# ESP07_Multi.net
KiCad netlist of a schematic drawn in EAGLE
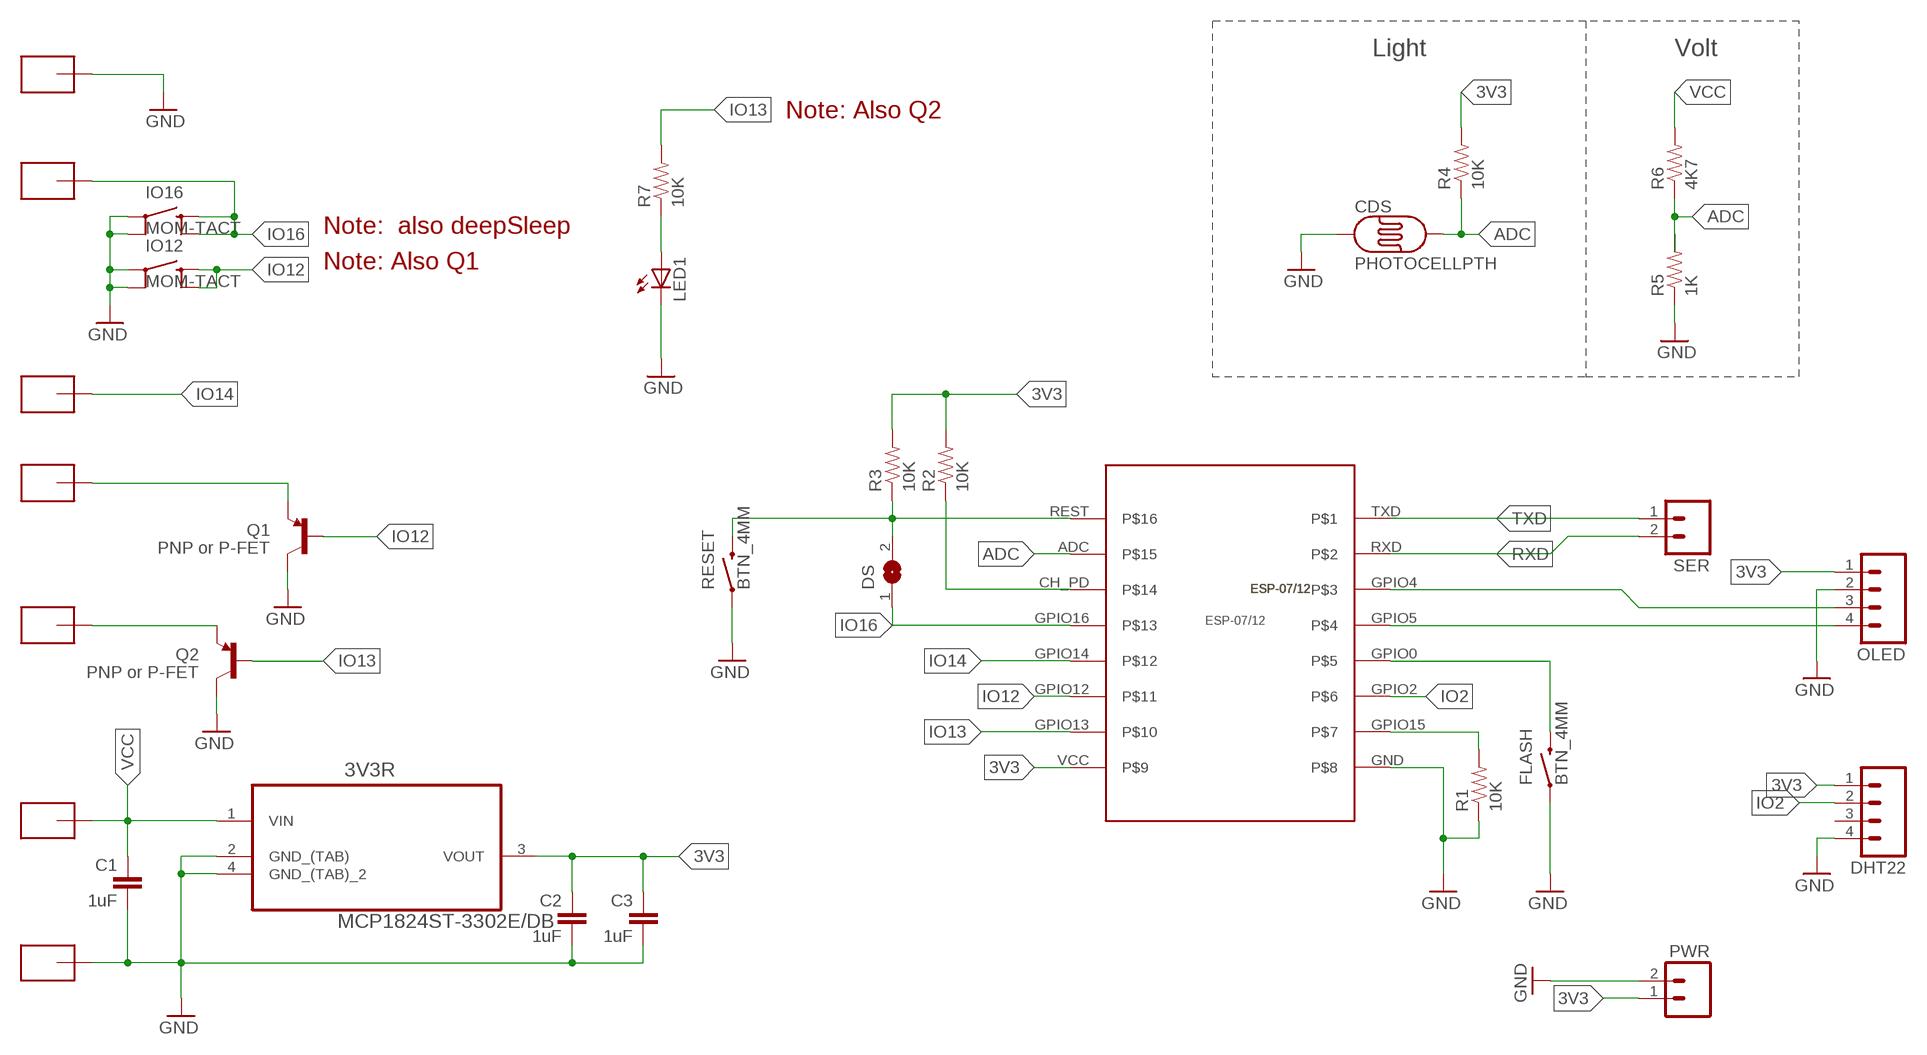
[diagram p0: schematic, sheet 1]

(export (version "E")
  (design (tool "Eeschema 10.0.6"))
  (components
    (comp (ref "3V3R")
      (value "MCP1824ST-3302E/DB")
      (footprint "eagle-import:SOT230P700X180-4N")
      (libsource (lib "eagle-import") (part "MCP1824ST-3302E/DB"))
    )
    (comp (ref "C1")
      (value "1uF")
      (footprint "eagle-import:0805-CAP")
      (libsource (lib "eagle-import") (part "CAP"))
    )
    (comp (ref "C2")
      (value "1uF")
      (footprint "eagle-import:0805-CAP")
      (libsource (lib "eagle-import") (part "CAP"))
    )
    (comp (ref "C3")
      (value "1uF")
      (footprint "eagle-import:0805-CAP")
      (libsource (lib "eagle-import") (part "CAP"))
    )
    (comp (ref "CDS")
      (value "PHOTOCELLPTH")
      (footprint "eagle-import:PHOTOCELL")
      (libsource (lib "eagle-import") (part "PHOTOCELLPTH"))
    )
    (comp (ref "DHT22")
      (value "M04PTH")
      (footprint "eagle-import:1X04")
      (libsource (lib "eagle-import") (part "M04PTH"))
    )
    (comp (ref "DS") (value "SJ") (footprint "eagle-import:SJ") (libsource (lib "eagle-import") (part "SJ")))
    (comp (ref "FLASH")
      (value "BTN_4MM")
      (footprint "eagle-import:BTN_4MM")
      (libsource (lib "eagle-import") (part "BTN_4MM"))
    )
    (comp (ref "IO12")
      (value "MOM-TACT")
      (footprint "eagle-import:TACTILE-SMD")
      (libsource (lib "eagle-import") (part "MOM-TACT"))
    )
    (comp (ref "IO16")
      (value "MOM-TACT")
      (footprint "eagle-import:TACTILE-SMD")
      (libsource (lib "eagle-import") (part "MOM-TACT"))
    )
    (comp (ref "LED1")
      (value "LEDCHIPLED_0805")
      (footprint "eagle-import:CHIPLED_0805")
      (libsource (lib "eagle-import") (part "LEDCHIPLED_0805"))
    )
    (comp (ref "OLED")
      (value "M04PTH")
      (footprint "eagle-import:1X04")
      (libsource (lib "eagle-import") (part "M04PTH"))
    )
    (comp (ref "PWR")
      (value "M02PTH")
      (footprint "eagle-import:1X02")
      (libsource (lib "eagle-import") (part "M02PTH"))
    )
    (comp (ref "Q1")
      (value "PNP or P-FET")
      (footprint "eagle-import:SOT23-3")
      (libsource (lib "eagle-import") (part "TRANSISTOR_PNPSMD"))
    )
    (comp (ref "Q2")
      (value "PNP or P-FET")
      (footprint "eagle-import:SOT23-3")
      (libsource (lib "eagle-import") (part "TRANSISTOR_PNPSMD"))
    )
    (comp (ref "R1")
      (value "10K")
      (footprint "eagle-import:0805")
      (libsource (lib "eagle-import") (part "RESISTOR0805-RES"))
    )
    (comp (ref "R2")
      (value "10K")
      (footprint "eagle-import:0805")
      (libsource (lib "eagle-import") (part "RESISTOR0805-RES"))
    )
    (comp (ref "R3")
      (value "10K")
      (footprint "eagle-import:0805")
      (libsource (lib "eagle-import") (part "RESISTOR0805-RES"))
    )
    (comp (ref "R4")
      (value "10K")
      (footprint "eagle-import:0805")
      (libsource (lib "eagle-import") (part "RESISTOR0805-RES"))
    )
    (comp (ref "R5")
      (value "1K")
      (footprint "eagle-import:0805")
      (libsource (lib "eagle-import") (part "RESISTOR0805-RES"))
    )
    (comp (ref "R6")
      (value "4K7")
      (footprint "eagle-import:0805")
      (libsource (lib "eagle-import") (part "RESISTOR0805-RES"))
    )
    (comp (ref "R7")
      (value "10K")
      (footprint "eagle-import:0805")
      (libsource (lib "eagle-import") (part "RESISTOR0805-RES"))
    )
    (comp (ref "RESET")
      (value "BTN_4MM")
      (footprint "eagle-import:BTN_4MM")
      (libsource (lib "eagle-import") (part "BTN_4MM"))
    )
    (comp (ref "SER")
      (value "M02PTH")
      (footprint "eagle-import:1X02")
      (libsource (lib "eagle-import") (part "M02PTH"))
    )
    (comp (ref "U$1")
      (value "ESP-07/12")
      (footprint "eagle-import:ESP-07_12")
      (libsource (lib "eagle-import") (part "ESP-07/12"))
    )
    (comp (ref "U$2")
      (value "SMD-PAD-SM")
      (footprint "eagle-import:SMD-PAD3")
      (libsource (lib "eagle-import") (part "SMD-PAD-SM"))
    )
    (comp (ref "U$3")
      (value "SMD-PAD-SM")
      (footprint "eagle-import:SMD-PAD3")
      (libsource (lib "eagle-import") (part "SMD-PAD-SM"))
    )
    (comp (ref "U$4")
      (value "SMD-PAD-SM")
      (footprint "eagle-import:SMD-PAD3")
      (libsource (lib "eagle-import") (part "SMD-PAD-SM"))
    )
    (comp (ref "U$5")
      (value "SMD-PAD-SM")
      (footprint "eagle-import:SMD-PAD3")
      (libsource (lib "eagle-import") (part "SMD-PAD-SM"))
    )
    (comp (ref "U$6")
      (value "SMD-PAD-SM")
      (footprint "eagle-import:SMD-PAD3")
      (libsource (lib "eagle-import") (part "SMD-PAD-SM"))
    )
    (comp (ref "U$7")
      (value "SMD-PAD-SM")
      (footprint "eagle-import:SMD-PAD3")
      (libsource (lib "eagle-import") (part "SMD-PAD-SM"))
    )
    (comp (ref "U$8")
      (value "SMD-PAD-SM")
      (footprint "eagle-import:SMD-PAD3")
      (libsource (lib "eagle-import") (part "SMD-PAD-SM"))
    )
  )
  (nets
    (net (code "1") (name "3V3") (class "Default")
      (node (ref "3V3R") (pin "3") (pinfunction "VOUT_3") (pintype "output"))
      (node (ref "C2") (pin "1") (pinfunction "1_1") (pintype "passive"))
      (node (ref "C3") (pin "1") (pinfunction "1_1") (pintype "passive"))
      (node (ref "DHT22") (pin "1") (pinfunction "1_1") (pintype "passive"))
      (node (ref "OLED") (pin "1") (pinfunction "1_1") (pintype "passive"))
      (node (ref "PWR") (pin "1") (pinfunction "1_1") (pintype "passive"))
      (node (ref "R2") (pin "2") (pinfunction "2_2") (pintype "passive"))
      (node (ref "R3") (pin "2") (pinfunction "2_2") (pintype "passive"))
      (node (ref "R4") (pin "2") (pinfunction "2_2") (pintype "passive"))
      (node (ref "U$1") (pin "VCC") (pinfunction "P$9_VCC") (pintype "bidirectional"))
    )
    (net (code "2") (name "ADC") (class "Default")
      (node (ref "CDS") (pin "2") (pinfunction "P$2_2") (pintype "bidirectional"))
      (node (ref "R4") (pin "1") (pinfunction "1_1") (pintype "passive"))
      (node (ref "R5") (pin "2") (pinfunction "2_2") (pintype "passive"))
      (node (ref "R6") (pin "1") (pinfunction "1_1") (pintype "passive"))
      (node (ref "U$1") (pin "ADC") (pinfunction "P$15_ADC") (pintype "bidirectional"))
    )
    (net (code "3") (name "GND") (class "Default")
      (node (ref "3V3R") (pin "2") (pinfunction "GND_(TAB)_2") (pintype "passive"))
      (node (ref "3V3R") (pin "4") (pinfunction "GND_(TAB)_2_4") (pintype "passive"))
      (node (ref "C1") (pin "2") (pinfunction "2_2") (pintype "passive"))
      (node (ref "C2") (pin "2") (pinfunction "2_2") (pintype "passive"))
      (node (ref "C3") (pin "2") (pinfunction "2_2") (pintype "passive"))
      (node (ref "CDS") (pin "1") (pinfunction "P$1_1") (pintype "bidirectional"))
      (node (ref "DHT22") (pin "4") (pinfunction "4_4") (pintype "passive"))
      (node (ref "FLASH") (pin "1") (pinfunction "1_1") (pintype "passive"))
      (node (ref "IO12") (pin "1") (pinfunction "1_1") (pintype "passive"))
      (node (ref "IO12") (pin "2") (pinfunction "3_2") (pintype "passive"))
      (node (ref "IO16") (pin "1") (pinfunction "1_1") (pintype "passive"))
      (node (ref "IO16") (pin "2") (pinfunction "3_2") (pintype "passive"))
      (node (ref "LED1") (pin "C") (pinfunction "C_C") (pintype "passive"))
      (node (ref "OLED") (pin "2") (pinfunction "2_2") (pintype "passive"))
      (node (ref "PWR") (pin "2") (pinfunction "2_2") (pintype "passive"))
      (node (ref "Q1") (pin "3") (pinfunction "C_3") (pintype "passive"))
      (node (ref "Q2") (pin "3") (pinfunction "C_3") (pintype "passive"))
      (node (ref "R1") (pin "1") (pinfunction "1_1") (pintype "passive"))
      (node (ref "R5") (pin "1") (pinfunction "1_1") (pintype "passive"))
      (node (ref "RESET") (pin "1") (pinfunction "1_1") (pintype "passive"))
      (node (ref "U$1") (pin "GND") (pinfunction "P$8_GND") (pintype "bidirectional"))
      (node (ref "U$2") (pin "P$1") (pinfunction "P$1_P$1") (pintype "bidirectional"))
      (node (ref "U$5") (pin "P$1") (pinfunction "P$1_P$1") (pintype "bidirectional"))
    )
    (net (code "4") (name "IO2") (class "Default")
      (node (ref "DHT22") (pin "2") (pinfunction "2_2") (pintype "passive"))
      (node (ref "U$1") (pin "GPIO2") (pinfunction "P$6_GPIO2") (pintype "bidirectional"))
    )
    (net (code "5") (name "IO12") (class "Default")
      (node (ref "IO12") (pin "3") (pinfunction "2_3") (pintype "passive"))
      (node (ref "IO12") (pin "4") (pinfunction "4_4") (pintype "passive"))
      (node (ref "Q1") (pin "1") (pinfunction "B_1") (pintype "passive"))
      (node (ref "U$1") (pin "GPIO12") (pinfunction "P$11_GPIO12") (pintype "bidirectional"))
    )
    (net (code "6") (name "IO13") (class "Default")
      (node (ref "Q2") (pin "1") (pinfunction "B_1") (pintype "passive"))
      (node (ref "R7") (pin "2") (pinfunction "2_2") (pintype "passive"))
      (node (ref "U$1") (pin "GPIO13") (pinfunction "P$10_GPIO13") (pintype "bidirectional"))
    )
    (net (code "7") (name "IO14") (class "Default")
      (node (ref "U$1") (pin "GPIO14") (pinfunction "P$12_GPIO14") (pintype "bidirectional"))
      (node (ref "U$4") (pin "P$1") (pinfunction "P$1_P$1") (pintype "bidirectional"))
    )
    (net (code "8") (name "IO16") (class "Default")
      (node (ref "DS") (pin "1") (pinfunction "1_1") (pintype "passive"))
      (node (ref "IO16") (pin "3") (pinfunction "2_3") (pintype "passive"))
      (node (ref "IO16") (pin "4") (pinfunction "4_4") (pintype "passive"))
      (node (ref "U$1") (pin "GPIO16") (pinfunction "P$13_GPIO16") (pintype "bidirectional"))
      (node (ref "U$6") (pin "P$1") (pinfunction "P$1_P$1") (pintype "bidirectional"))
    )
    (net (code "9") (name "Net-(LED1-PadA)") (class "Default")
      (node (ref "LED1") (pin "A") (pinfunction "A_A") (pintype "passive"))
      (node (ref "R7") (pin "1") (pinfunction "1_1") (pintype "passive"))
    )
    (net (code "10") (name "Net-(Q1-E)") (class "Default")
      (node (ref "Q1") (pin "2") (pinfunction "E_2") (pintype "passive"))
      (node (ref "U$7") (pin "P$1") (pinfunction "P$1_P$1") (pintype "bidirectional"))
    )
    (net (code "11") (name "Net-(Q2-E)") (class "Default")
      (node (ref "Q2") (pin "2") (pinfunction "E_2") (pintype "passive"))
      (node (ref "U$8") (pin "P$1") (pinfunction "P$1_P$1") (pintype "bidirectional"))
    )
    (net (code "12") (name "Net-(U$1-P$3)") (class "Default")
      (node (ref "OLED") (pin "3") (pinfunction "3_3") (pintype "passive"))
      (node (ref "U$1") (pin "GPIO4") (pinfunction "P$3_GPIO4") (pintype "bidirectional"))
    )
    (net (code "13") (name "Net-(U$1-P$4)") (class "Default")
      (node (ref "OLED") (pin "4") (pinfunction "4_4") (pintype "passive"))
      (node (ref "U$1") (pin "GPIO5") (pinfunction "P$4_GPIO5") (pintype "bidirectional"))
    )
    (net (code "14") (name "Net-(U$1-P$5)") (class "Default")
      (node (ref "FLASH") (pin "2") (pinfunction "2_2") (pintype "passive"))
      (node (ref "U$1") (pin "GPIO0") (pinfunction "P$5_GPIO0") (pintype "bidirectional"))
    )
    (net (code "15") (name "Net-(U$1-P$7)") (class "Default")
      (node (ref "R1") (pin "2") (pinfunction "2_2") (pintype "passive"))
      (node (ref "U$1") (pin "GPIO15") (pinfunction "P$7_GPIO15") (pintype "bidirectional"))
    )
    (net (code "16") (name "Net-(U$1-P$14)") (class "Default")
      (node (ref "R2") (pin "1") (pinfunction "1_1") (pintype "passive"))
      (node (ref "U$1") (pin "CH_PD") (pinfunction "P$14_CH_PD") (pintype "bidirectional"))
    )
    (net (code "17") (name "Net-(U$1-P$16)") (class "Default")
      (node (ref "DS") (pin "2") (pinfunction "2_2") (pintype "passive"))
      (node (ref "R3") (pin "1") (pinfunction "1_1") (pintype "passive"))
      (node (ref "RESET") (pin "2") (pinfunction "2_2") (pintype "passive"))
      (node (ref "U$1") (pin "REST") (pinfunction "P$16_REST") (pintype "bidirectional"))
    )
    (net (code "18") (name "RXD") (class "Default")
      (node (ref "SER") (pin "2") (pinfunction "2_2") (pintype "passive"))
      (node (ref "U$1") (pin "RXD") (pinfunction "P$2_RXD") (pintype "bidirectional"))
    )
    (net (code "19") (name "TXD") (class "Default")
      (node (ref "SER") (pin "1") (pinfunction "1_1") (pintype "passive"))
      (node (ref "U$1") (pin "TXD") (pinfunction "P$1_TXD") (pintype "bidirectional"))
    )
    (net (code "20") (name "VCC") (class "Default")
      (node (ref "3V3R") (pin "1") (pinfunction "VIN_1") (pintype "input"))
      (node (ref "C1") (pin "1") (pinfunction "1_1") (pintype "passive"))
      (node (ref "R6") (pin "2") (pinfunction "2_2") (pintype "passive"))
      (node (ref "U$3") (pin "P$1") (pinfunction "P$1_P$1") (pintype "bidirectional"))
    )
    (net (code "21") (name "unconnected-(DHT22-Pad3)") (class "Default")
      (node (ref "DHT22") (pin "3") (pinfunction "3_3") (pintype "passive"))
    )
  )
)
